# Adafruit_Ultimate_GPS_Featherwing.net
KiCad netlist of a schematic drawn in EAGLE
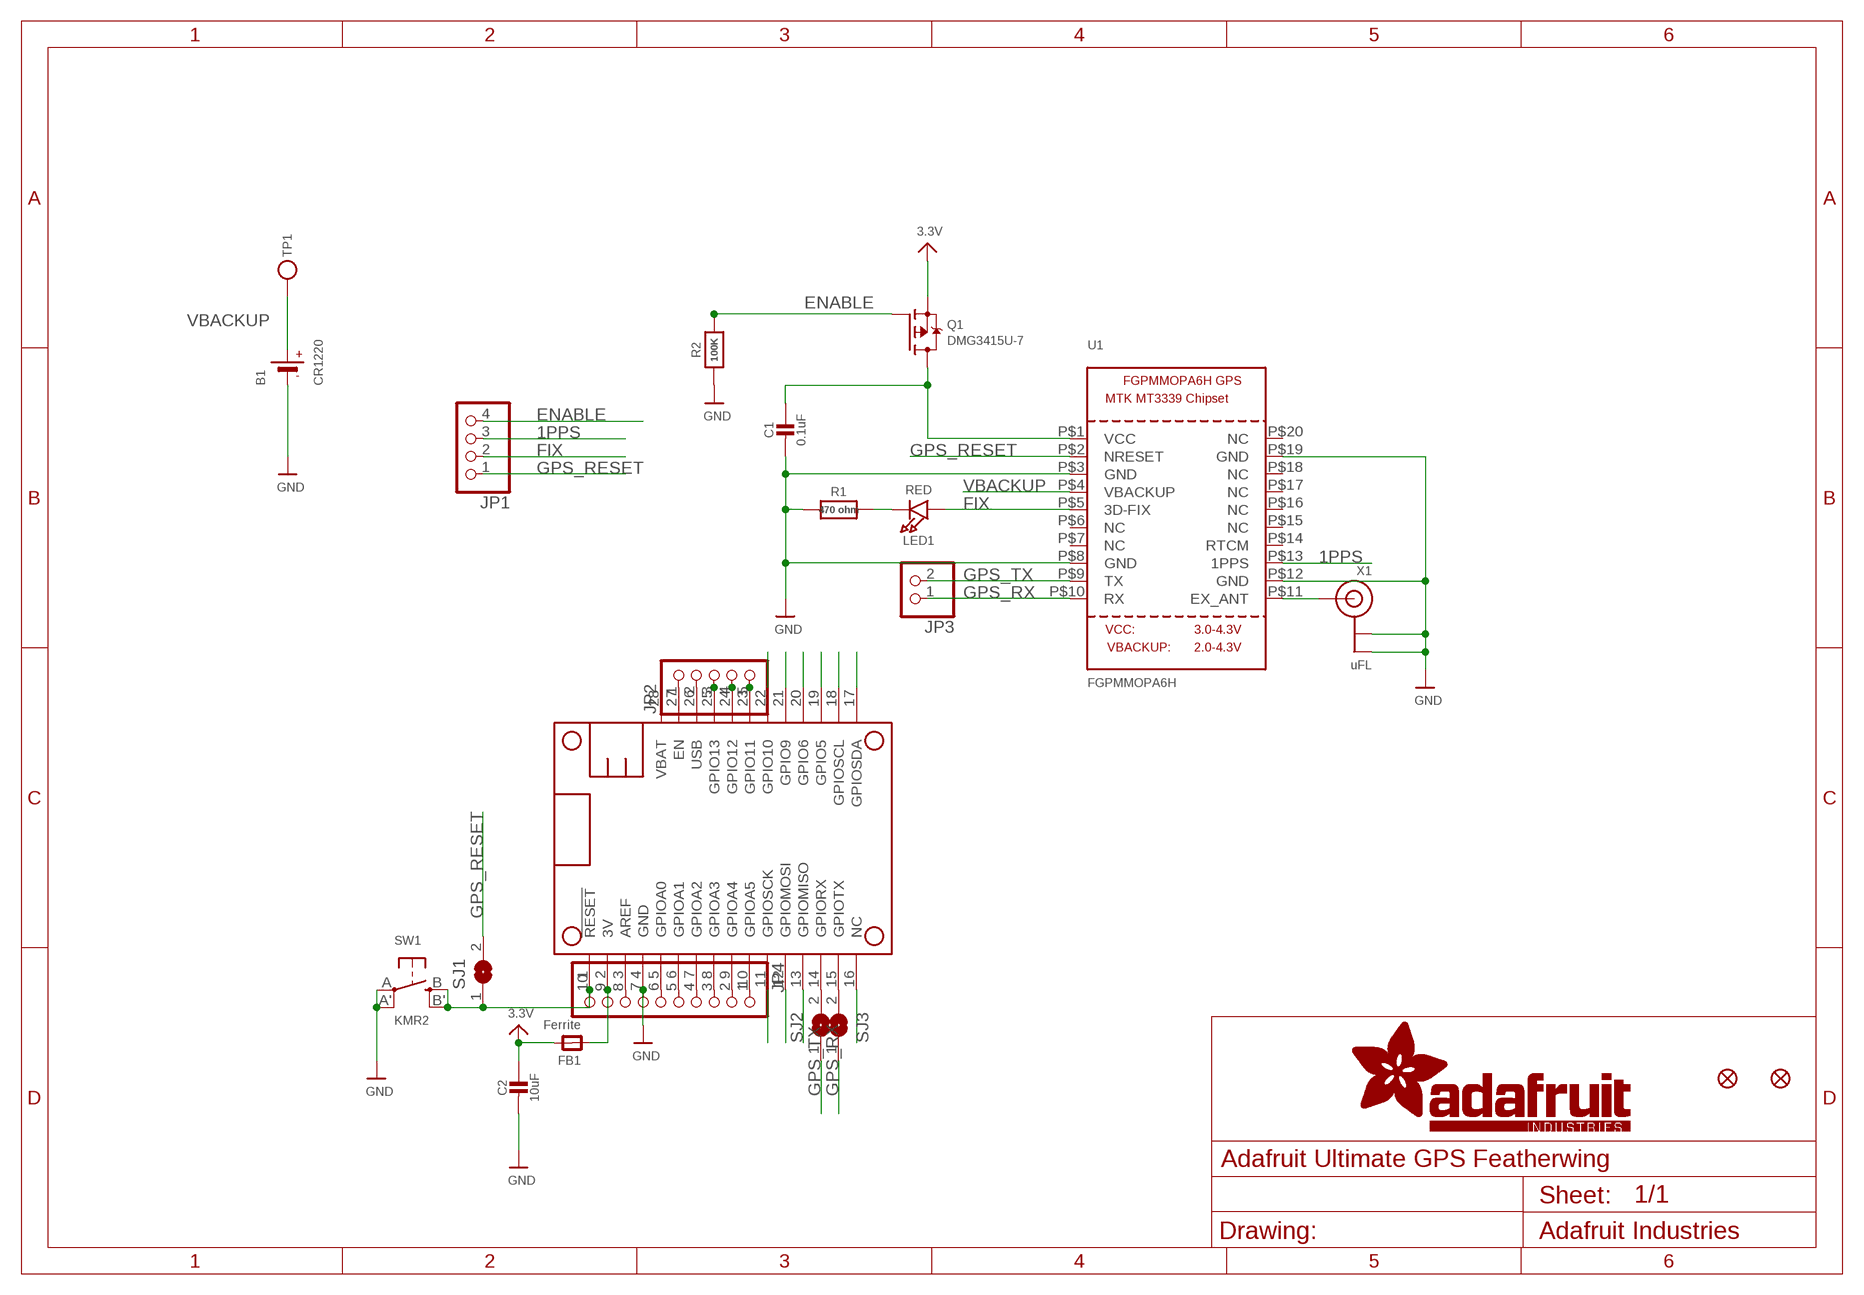
[diagram p0: schematic, sheet 1]

(export (version "E")
  (design (tool "Eeschema 10.0.6"))
  (components
    (comp (ref "B1")
      (value "CR1220")
      (footprint "eagle-import:CR1220-2")
      (libsource (lib "eagle-import") (part "BATTERYCR1220_2"))
    )
    (comp (ref "C1")
      (value "0.1uF")
      (footprint "eagle-import:0805-NO")
      (libsource (lib "eagle-import") (part "CAP_CERAMIC0805-NOOUTLINE"))
    )
    (comp (ref "C2")
      (value "10uF")
      (footprint "eagle-import:0805-NO")
      (libsource (lib "eagle-import") (part "CAP_CERAMIC0805-NOOUTLINE"))
    )
    (comp (ref "FB1")
      (value "Ferrite")
      (footprint "eagle-import:0805-NO")
      (libsource (lib "eagle-import") (part "FERRITE-0805NO"))
    )
    (comp (ref "FID1")
      (value "FIDUCIAL\"\"")
      (footprint "eagle-import:FIDUCIAL_1MM")
      (libsource (lib "eagle-import") (part "FIDUCIAL{dblquote}{dblquote}"))
    )
    (comp (ref "FID2")
      (value "FIDUCIAL\"\"")
      (footprint "eagle-import:FIDUCIAL_1MM")
      (libsource (lib "eagle-import") (part "FIDUCIAL{dblquote}{dblquote}"))
    )
    (comp (ref "JP1")
      (value "HEADER-1X4ROUND")
      (footprint "eagle-import:1X04_ROUND")
      (libsource (lib "eagle-import") (part "HEADER-1X4ROUND"))
    )
    (comp (ref "JP2")
      (value "HEADER-1X570MIL")
      (footprint "eagle-import:1X05_ROUND_70")
      (libsource (lib "eagle-import") (part "HEADER-1X570MIL"))
    )
    (comp (ref "JP3")
      (value "HEADER-1X2ROUND")
      (footprint "eagle-import:1X02_ROUND")
      (libsource (lib "eagle-import") (part "HEADER-1X2ROUND"))
    )
    (comp (ref "JP4")
      (value "HEADER-1X10ROUND")
      (footprint "eagle-import:1X10_ROUND")
      (libsource (lib "eagle-import") (part "HEADER-1X10ROUND"))
    )
    (comp (ref "LED1")
      (value "RED")
      (footprint "eagle-import:CHIPLED_0805_NOOUTLINE")
      (libsource (lib "eagle-import") (part "LED0805_NOOUTLINE"))
    )
    (comp (ref "MS1")
      (value "FEATHERWING")
      (footprint "eagle-import:FEATHERWING")
      (libsource (lib "eagle-import") (part "FEATHERWING"))
    )
    (comp (ref "Q1")
      (value "DMG3415U-7")
      (footprint "eagle-import:SOT23-WIDE")
      (libsource (lib "eagle-import") (part "MOSFET-PWIDE"))
    )
    (comp (ref "R1")
      (value "470 ohm")
      (footprint "eagle-import:0805-NO")
      (libsource (lib "eagle-import") (part "RESISTOR0805_NOOUTLINE"))
    )
    (comp (ref "R2")
      (value "100K")
      (footprint "eagle-import:0805-NO")
      (libsource (lib "eagle-import") (part "RESISTOR0805_NOOUTLINE"))
    )
    (comp (ref "SJ1")
      (value "SOLDERJUMPER")
      (footprint "eagle-import:SOLDERJUMPER_ARROW_NOPASTE")
      (libsource (lib "eagle-import") (part "SOLDERJUMPER"))
    )
    (comp (ref "SJ2")
      (value "SOLDERJUMPERCLOSED")
      (footprint "eagle-import:SOLDERJUMPER_CLOSEDWIRE")
      (libsource (lib "eagle-import") (part "SOLDERJUMPERCLOSED"))
    )
    (comp (ref "SJ3")
      (value "SOLDERJUMPERCLOSED")
      (footprint "eagle-import:SOLDERJUMPER_CLOSEDWIRE")
      (libsource (lib "eagle-import") (part "SOLDERJUMPERCLOSED"))
    )
    (comp (ref "SW1")
      (value "KMR2")
      (footprint "eagle-import:BTN_KMR2_4.6X2.8")
      (libsource (lib "eagle-import") (part "SWITCH_TACT_SMT4.6X2.8"))
    )
    (comp (ref "TP1")
      (value "TESTPOINTROUND1.5MM")
      (footprint "eagle-import:TESTPOINT_ROUND_1.5MM")
      (libsource (lib "eagle-import") (part "TESTPOINTROUND1.5MM"))
    )
    (comp (ref "U1")
      (value "FGPMMOPA6H")
      (footprint "eagle-import:FGPMMOPA6H")
      (libsource (lib "eagle-import") (part "GPS_FGPMMOPA6H"))
    )
    (comp (ref "X1")
      (value "uFL")
      (footprint "eagle-import:U.FL")
      (libsource (lib "eagle-import") (part "ANTENNA_U.FL"))
    )
  )
  (nets
    (net (code "1") (name "/1PPS") (class "Default")
      (node (ref "JP1") (pin "3") (pinfunction "3_3") (pintype "passive"))
      (node (ref "U1") (pin "P$13") (pinfunction "1PPS_P$13") (pintype "bidirectional"))
    )
    (net (code "2") (name "/ENABLE") (class "Default")
      (node (ref "JP1") (pin "4") (pinfunction "4_4") (pintype "passive"))
      (node (ref "Q1") (pin "1") (pinfunction "G_1") (pintype "passive"))
      (node (ref "R2") (pin "2") (pinfunction "2_2") (pintype "passive"))
    )
    (net (code "3") (name "/FIX") (class "Default")
      (node (ref "JP1") (pin "2") (pinfunction "2_2") (pintype "passive"))
      (node (ref "LED1") (pin "A") (pinfunction "A_A") (pintype "passive"))
      (node (ref "U1") (pin "P$5") (pinfunction "3D-FIX_P$5") (pintype "bidirectional"))
    )
    (net (code "4") (name "/GPS_RESET") (class "Default")
      (node (ref "JP1") (pin "1") (pinfunction "1_1") (pintype "passive"))
      (node (ref "SJ1") (pin "2") (pinfunction "2_2") (pintype "passive"))
      (node (ref "U1") (pin "P$2") (pinfunction "NRESET_P$2") (pintype "bidirectional"))
    )
    (net (code "5") (name "/GPS_RX") (class "Default")
      (node (ref "JP3") (pin "1") (pinfunction "1_1") (pintype "passive"))
      (node (ref "SJ3") (pin "1") (pinfunction "1_1") (pintype "passive"))
      (node (ref "U1") (pin "P$10") (pinfunction "RX_P$10") (pintype "bidirectional"))
    )
    (net (code "6") (name "/GPS_TX") (class "Default")
      (node (ref "JP3") (pin "2") (pinfunction "2_2") (pintype "passive"))
      (node (ref "SJ2") (pin "1") (pinfunction "1_1") (pintype "passive"))
      (node (ref "U1") (pin "P$9") (pinfunction "TX_P$9") (pintype "bidirectional"))
    )
    (net (code "7") (name "/VBACKUP") (class "Default")
      (node (ref "B1") (pin "+") (pinfunction "+_+") (pintype "passive"))
      (node (ref "TP1") (pin "P$1") (pinfunction "P$1_P$1") (pintype "bidirectional"))
      (node (ref "U1") (pin "P$4") (pinfunction "VBACKUP_P$4") (pintype "bidirectional"))
    )
    (net (code "8") (name "/VBAT") (class "Default")
      (node (ref "MS1") (pin "28") (pinfunction "VBAT_28") (pintype "power_in"))
    )
    (net (code "9") (name "3.3V") (class "Default")
      (node (ref "C2") (pin "1") (pinfunction "1_1") (pintype "passive"))
      (node (ref "FB1") (pin "2") (pinfunction "P$2_2") (pintype "passive"))
      (node (ref "Q1") (pin "2") (pinfunction "S_2") (pintype "passive"))
    )
    (net (code "10") (name "GND") (class "Default")
      (node (ref "B1") (pin "-") (pinfunction "-_-") (pintype "passive"))
      (node (ref "C1") (pin "2") (pinfunction "2_2") (pintype "passive"))
      (node (ref "C2") (pin "2") (pinfunction "2_2") (pintype "passive"))
      (node (ref "JP4") (pin "7") (pinfunction "7_7") (pintype "passive"))
      (node (ref "MS1") (pin "4") (pinfunction "GND_4") (pintype "power_in"))
      (node (ref "R1") (pin "1") (pinfunction "1_1") (pintype "passive"))
      (node (ref "R2") (pin "1") (pinfunction "1_1") (pintype "passive"))
      (node (ref "SW1") (pin "A") (pinfunction "P_A") (pintype "passive"))
      (node (ref "SW1") (pin "A'") (pinfunction "P1_A'") (pintype "passive"))
      (node (ref "U1") (pin "P$12") (pinfunction "GND_P$12") (pintype "bidirectional"))
      (node (ref "U1") (pin "P$19") (pinfunction "GND_P$19") (pintype "bidirectional"))
      (node (ref "U1") (pin "P$3") (pinfunction "GND_P$3") (pintype "bidirectional"))
      (node (ref "U1") (pin "P$8") (pinfunction "GND_P$8") (pintype "bidirectional"))
      (node (ref "X1") (pin "1") (pinfunction "GND_1") (pintype "passive"))
      (node (ref "X1") (pin "2") (pinfunction "GND_2") (pintype "passive"))
    )
    (net (code "11") (name "Net-(FB1-P$1)") (class "Default")
      (node (ref "FB1") (pin "1") (pinfunction "P$1_1") (pintype "passive"))
      (node (ref "JP4") (pin "9") (pinfunction "9_9") (pintype "passive"))
      (node (ref "MS1") (pin "2") (pinfunction "3V_2") (pintype "power_in"))
    )
    (net (code "12") (name "Net-(LED1-PadC)") (class "Default")
      (node (ref "LED1") (pin "C") (pinfunction "C_C") (pintype "passive"))
      (node (ref "R1") (pin "2") (pinfunction "2_2") (pintype "passive"))
    )
    (net (code "13") (name "Net-(MS1-AREF)") (class "Default")
      (node (ref "JP4") (pin "8") (pinfunction "8_8") (pintype "passive"))
      (node (ref "MS1") (pin "3") (pinfunction "AREF_3") (pintype "passive"))
    )
    (net (code "14") (name "Net-(MS1-EN)") (class "Default")
      (node (ref "JP2") (pin "1") (pinfunction "1_1") (pintype "passive"))
      (node (ref "MS1") (pin "27") (pinfunction "EN_27") (pintype "passive"))
    )
    (net (code "15") (name "Net-(MS1-GPIO11)") (class "Default")
      (node (ref "JP2") (pin "5") (pinfunction "5_5") (pintype "passive"))
      (node (ref "MS1") (pin "23") (pinfunction "GPIO11_23") (pintype "bidirectional"))
    )
    (net (code "16") (name "Net-(MS1-GPIO12)") (class "Default")
      (node (ref "JP2") (pin "4") (pinfunction "4_4") (pintype "passive"))
      (node (ref "MS1") (pin "24") (pinfunction "GPIO12_24") (pintype "bidirectional"))
    )
    (net (code "17") (name "Net-(MS1-GPIO13)") (class "Default")
      (node (ref "JP2") (pin "3") (pinfunction "3_3") (pintype "passive"))
      (node (ref "MS1") (pin "25") (pinfunction "GPIO13_25") (pintype "bidirectional"))
    )
    (net (code "18") (name "Net-(MS1-GPIOA0)") (class "Default")
      (node (ref "JP4") (pin "6") (pinfunction "6_6") (pintype "passive"))
      (node (ref "MS1") (pin "5") (pinfunction "GPIOA0_5") (pintype "bidirectional"))
    )
    (net (code "19") (name "Net-(MS1-GPIOA1)") (class "Default")
      (node (ref "JP4") (pin "5") (pinfunction "5_5") (pintype "passive"))
      (node (ref "MS1") (pin "6") (pinfunction "GPIOA1_6") (pintype "bidirectional"))
    )
    (net (code "20") (name "Net-(MS1-GPIOA2)") (class "Default")
      (node (ref "JP4") (pin "4") (pinfunction "4_4") (pintype "passive"))
      (node (ref "MS1") (pin "7") (pinfunction "GPIOA2_7") (pintype "bidirectional"))
    )
    (net (code "21") (name "Net-(MS1-GPIOA3)") (class "Default")
      (node (ref "JP4") (pin "3") (pinfunction "3_3") (pintype "passive"))
      (node (ref "MS1") (pin "8") (pinfunction "GPIOA3_8") (pintype "bidirectional"))
    )
    (net (code "22") (name "Net-(MS1-GPIOA4)") (class "Default")
      (node (ref "JP4") (pin "2") (pinfunction "2_2") (pintype "passive"))
      (node (ref "MS1") (pin "9") (pinfunction "GPIOA4_9") (pintype "bidirectional"))
    )
    (net (code "23") (name "Net-(MS1-GPIOA5)") (class "Default")
      (node (ref "JP4") (pin "1") (pinfunction "1_1") (pintype "passive"))
      (node (ref "MS1") (pin "10") (pinfunction "GPIOA5_10") (pintype "bidirectional"))
    )
    (net (code "24") (name "Net-(MS1-GPIORX)") (class "Default")
      (node (ref "MS1") (pin "14") (pinfunction "GPIORX_14") (pintype "bidirectional"))
      (node (ref "SJ2") (pin "2") (pinfunction "2_2") (pintype "passive"))
    )
    (net (code "25") (name "Net-(MS1-GPIOTX)") (class "Default")
      (node (ref "MS1") (pin "15") (pinfunction "GPIOTX_15") (pintype "bidirectional"))
      (node (ref "SJ3") (pin "2") (pinfunction "2_2") (pintype "passive"))
    )
    (net (code "26") (name "Net-(MS1-USB)") (class "Default")
      (node (ref "JP2") (pin "2") (pinfunction "2_2") (pintype "passive"))
      (node (ref "MS1") (pin "26") (pinfunction "USB_26") (pintype "power_in"))
    )
    (net (code "27") (name "Net-(MS1-~{RESET})") (class "Default")
      (node (ref "JP4") (pin "10") (pinfunction "10_10") (pintype "passive"))
      (node (ref "MS1") (pin "1") (pinfunction "~{RESET}_1") (pintype "input"))
      (node (ref "SJ1") (pin "1") (pinfunction "1_1") (pintype "passive"))
      (node (ref "SW1") (pin "B") (pinfunction "S_B") (pintype "passive"))
      (node (ref "SW1") (pin "B'") (pinfunction "S1_B'") (pintype "passive"))
    )
    (net (code "28") (name "Net-(Q1-D)") (class "Default")
      (node (ref "C1") (pin "1") (pinfunction "1_1") (pintype "passive"))
      (node (ref "Q1") (pin "3") (pinfunction "D_3") (pintype "passive"))
      (node (ref "U1") (pin "P$1") (pinfunction "VCC_P$1") (pintype "bidirectional"))
    )
    (net (code "29") (name "Net-(U1-EX_ANT)") (class "Default")
      (node (ref "U1") (pin "P$11") (pinfunction "EX_ANT_P$11") (pintype "bidirectional"))
      (node (ref "X1") (pin "3") (pinfunction "SIGNAL_3") (pintype "passive"))
    )
    (net (code "30") (name "unconnected-(MS1-GPIO5-Pad19)") (class "Default")
      (node (ref "MS1") (pin "19") (pinfunction "GPIO5_19") (pintype "bidirectional"))
    )
    (net (code "31") (name "unconnected-(MS1-GPIO6-Pad20)") (class "Default")
      (node (ref "MS1") (pin "20") (pinfunction "GPIO6_20") (pintype "bidirectional"))
    )
    (net (code "32") (name "unconnected-(MS1-GPIO9-Pad21)") (class "Default")
      (node (ref "MS1") (pin "21") (pinfunction "GPIO9_21") (pintype "bidirectional"))
    )
    (net (code "33") (name "unconnected-(MS1-GPIO10-Pad22)") (class "Default")
      (node (ref "MS1") (pin "22") (pinfunction "GPIO10_22") (pintype "bidirectional"))
    )
    (net (code "34") (name "unconnected-(MS1-GPIOMISO-Pad13)") (class "Default")
      (node (ref "MS1") (pin "13") (pinfunction "GPIOMISO_13") (pintype "bidirectional"))
    )
    (net (code "35") (name "unconnected-(MS1-GPIOMOSI-Pad12)") (class "Default")
      (node (ref "MS1") (pin "12") (pinfunction "GPIOMOSI_12") (pintype "bidirectional"))
    )
    (net (code "36") (name "unconnected-(MS1-GPIOSCK-Pad11)") (class "Default")
      (node (ref "MS1") (pin "11") (pinfunction "GPIOSCK_11") (pintype "bidirectional"))
    )
    (net (code "37") (name "unconnected-(MS1-GPIOSCL-Pad18)") (class "Default")
      (node (ref "MS1") (pin "18") (pinfunction "GPIOSCL_18") (pintype "bidirectional"))
    )
    (net (code "38") (name "unconnected-(MS1-GPIOSDA-Pad17)") (class "Default")
      (node (ref "MS1") (pin "17") (pinfunction "GPIOSDA_17") (pintype "bidirectional"))
    )
    (net (code "39") (name "unconnected-(MS1-NC-Pad16)") (class "Default")
      (node (ref "MS1") (pin "16") (pinfunction "NC_16") (pintype "passive"))
    )
    (net (code "40") (name "unconnected-(U1-NC-PadP$6)") (class "Default")
      (node (ref "U1") (pin "P$6") (pinfunction "NC_P$6") (pintype "bidirectional"))
    )
    (net (code "41") (name "unconnected-(U1-NC-PadP$7)") (class "Default")
      (node (ref "U1") (pin "P$7") (pinfunction "NC_P$7") (pintype "bidirectional"))
    )
    (net (code "42") (name "unconnected-(U1-NC-PadP$15)") (class "Default")
      (node (ref "U1") (pin "P$15") (pinfunction "NC_P$15") (pintype "bidirectional"))
    )
    (net (code "43") (name "unconnected-(U1-NC-PadP$16)") (class "Default")
      (node (ref "U1") (pin "P$16") (pinfunction "NC_P$16") (pintype "bidirectional"))
    )
    (net (code "44") (name "unconnected-(U1-NC-PadP$17)") (class "Default")
      (node (ref "U1") (pin "P$17") (pinfunction "NC_P$17") (pintype "bidirectional"))
    )
    (net (code "45") (name "unconnected-(U1-NC-PadP$18)") (class "Default")
      (node (ref "U1") (pin "P$18") (pinfunction "NC_P$18") (pintype "bidirectional"))
    )
    (net (code "46") (name "unconnected-(U1-NC-PadP$20)") (class "Default")
      (node (ref "U1") (pin "P$20") (pinfunction "NC_P$20") (pintype "bidirectional"))
    )
    (net (code "47") (name "unconnected-(U1-RTCM-PadP$14)") (class "Default")
      (node (ref "U1") (pin "P$14") (pinfunction "RTCM_P$14") (pintype "bidirectional"))
    )
  )
)
